# design.net
KiCad netlist of a schematic drawn in Altium Designer
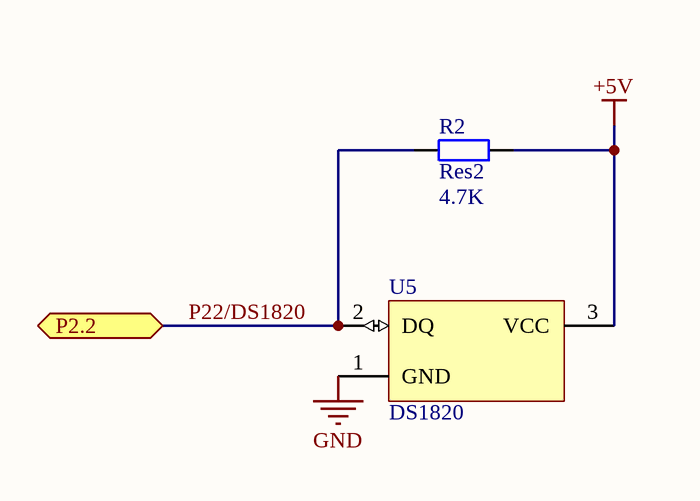
[diagram p0: 温度传感器模块.SchDoc]

(export (version "E")
  (design (tool "Eeschema 10.0.6"))
  (components
    (comp (ref "R2")
      (value "Res2")
      (footprint "AXIAL-0.4")
      (description "Resistor")
      (fields (field (name "ALTIUM_VALUE") "4.7K") (field (name "PUBLISHER") "Altium Limited"))
      (libsource (lib "Miscellaneous Devices") (part "Res2"))
    )
    (comp (ref "U5")
      (value "DS1820")
      (footprint "PR35")
      (description "1-Wire Digital Thermometer")
      (fields (field (name "PUBLISHER") "Altium Limited"))
      (libsource (lib "Dallas Sensor Temperature Sensor") (part "DS1820"))
    )
  )
  (nets
    (net (code "1") (name "+5V") (class "Default")
      (node (ref "R2") (pin "2") (pinfunction "2_2") (pintype "passive"))
      (node (ref "U5") (pin "3") (pinfunction "VCC_3") (pintype "power_in"))
    )
    (net (code "2") (name "/P22{slash}DS1820") (class "Default")
      (node (ref "R2") (pin "1") (pinfunction "1_1") (pintype "passive"))
      (node (ref "U5") (pin "2") (pinfunction "DQ_2") (pintype "bidirectional"))
    )
    (net (code "3") (name "GND") (class "Default")
      (node (ref "U5") (pin "1") (pinfunction "GND_1") (pintype "power_in"))
    )
  )
)
